# SensorBoard.net
KiCad netlist of a schematic drawn in EAGLE
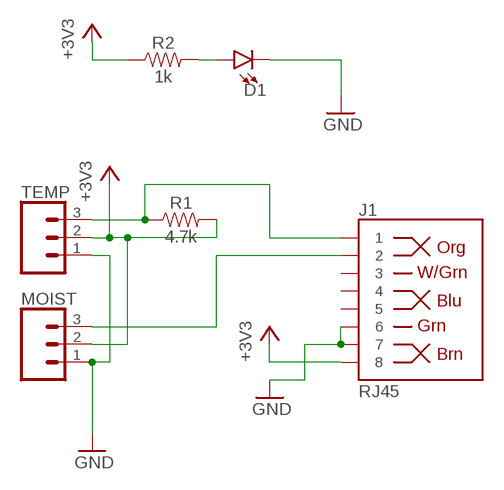
[diagram p0: schematic, sheet 1]

(export (version "E")
  (design (tool "Eeschema 10.0.6"))
  (components
    (comp (ref "D1")
      (value "LED3MM")
      (footprint "eagle-import:LED_3MM")
      (libsource (lib "eagle-import") (part "LED3MM"))
    )
    (comp (ref "J1")
      (value "RJ45")
      (footprint "eagle-import:RJ45-8")
      (libsource (lib "eagle-import") (part "RJ45-8"))
    )
    (comp (ref "MOIST")
      (value "CONN_03")
      (footprint "eagle-import:1X03")
      (libsource (lib "eagle-import") (part "CONN_03"))
    )
    (comp (ref "R1")
      (value "4.7k")
      (footprint "eagle-import:AXIAL-0.3")
      (libsource (lib "eagle-import") (part "1KOHM-HORIZ-1/4W-1%"))
    )
    (comp (ref "R2")
      (value "1k")
      (footprint "eagle-import:AXIAL-0.3")
      (libsource (lib "eagle-import") (part "1KOHM-HORIZ-1/4W-1%"))
    )
    (comp (ref "TEMP")
      (value "CONN_03")
      (footprint "eagle-import:1X03")
      (libsource (lib "eagle-import") (part "CONN_03"))
    )
  )
  (nets
    (net (code "1") (name "+3V3") (class "Default")
      (node (ref "J1") (pin "8") (pinfunction "8_8") (pintype "bidirectional"))
      (node (ref "MOIST") (pin "2") (pinfunction "2_2") (pintype "passive"))
      (node (ref "R1") (pin "P$2") (pinfunction "2_P$2") (pintype "passive"))
      (node (ref "R2") (pin "P$1") (pinfunction "1_P$1") (pintype "passive"))
      (node (ref "TEMP") (pin "2") (pinfunction "2_2") (pintype "passive"))
    )
    (net (code "2") (name "GND") (class "Default")
      (node (ref "D1") (pin "K") (pinfunction "C_K") (pintype "passive"))
      (node (ref "J1") (pin "6") (pinfunction "6_6") (pintype "bidirectional"))
      (node (ref "J1") (pin "7") (pinfunction "7_7") (pintype "bidirectional"))
      (node (ref "MOIST") (pin "1") (pinfunction "1_1") (pintype "passive"))
      (node (ref "TEMP") (pin "1") (pinfunction "1_1") (pintype "passive"))
    )
    (net (code "3") (name "Net-(J1-Pad2)") (class "Default")
      (node (ref "J1") (pin "2") (pinfunction "2_2") (pintype "bidirectional"))
      (node (ref "MOIST") (pin "3") (pinfunction "3_3") (pintype "passive"))
    )
    (net (code "4") (name "Net-(R1-1)") (class "Default")
      (node (ref "J1") (pin "1") (pinfunction "1_1") (pintype "bidirectional"))
      (node (ref "R1") (pin "P$1") (pinfunction "1_P$1") (pintype "passive"))
      (node (ref "TEMP") (pin "3") (pinfunction "3_3") (pintype "passive"))
    )
    (net (code "5") (name "Net-(R2-2)") (class "Default")
      (node (ref "D1") (pin "A") (pinfunction "A_A") (pintype "passive"))
      (node (ref "R2") (pin "P$2") (pinfunction "2_P$2") (pintype "passive"))
    )
    (net (code "6") (name "unconnected-(J1-Pad3)") (class "Default")
      (node (ref "J1") (pin "3") (pinfunction "3_3") (pintype "bidirectional"))
    )
    (net (code "7") (name "unconnected-(J1-Pad4)") (class "Default")
      (node (ref "J1") (pin "4") (pinfunction "4_4") (pintype "bidirectional"))
    )
    (net (code "8") (name "unconnected-(J1-Pad5)") (class "Default")
      (node (ref "J1") (pin "5") (pinfunction "5_5") (pintype "bidirectional"))
    )
  )
)
